# STC15F104_IR_RelayControl.net
KiCad netlist of a schematic drawn in Altium Designer
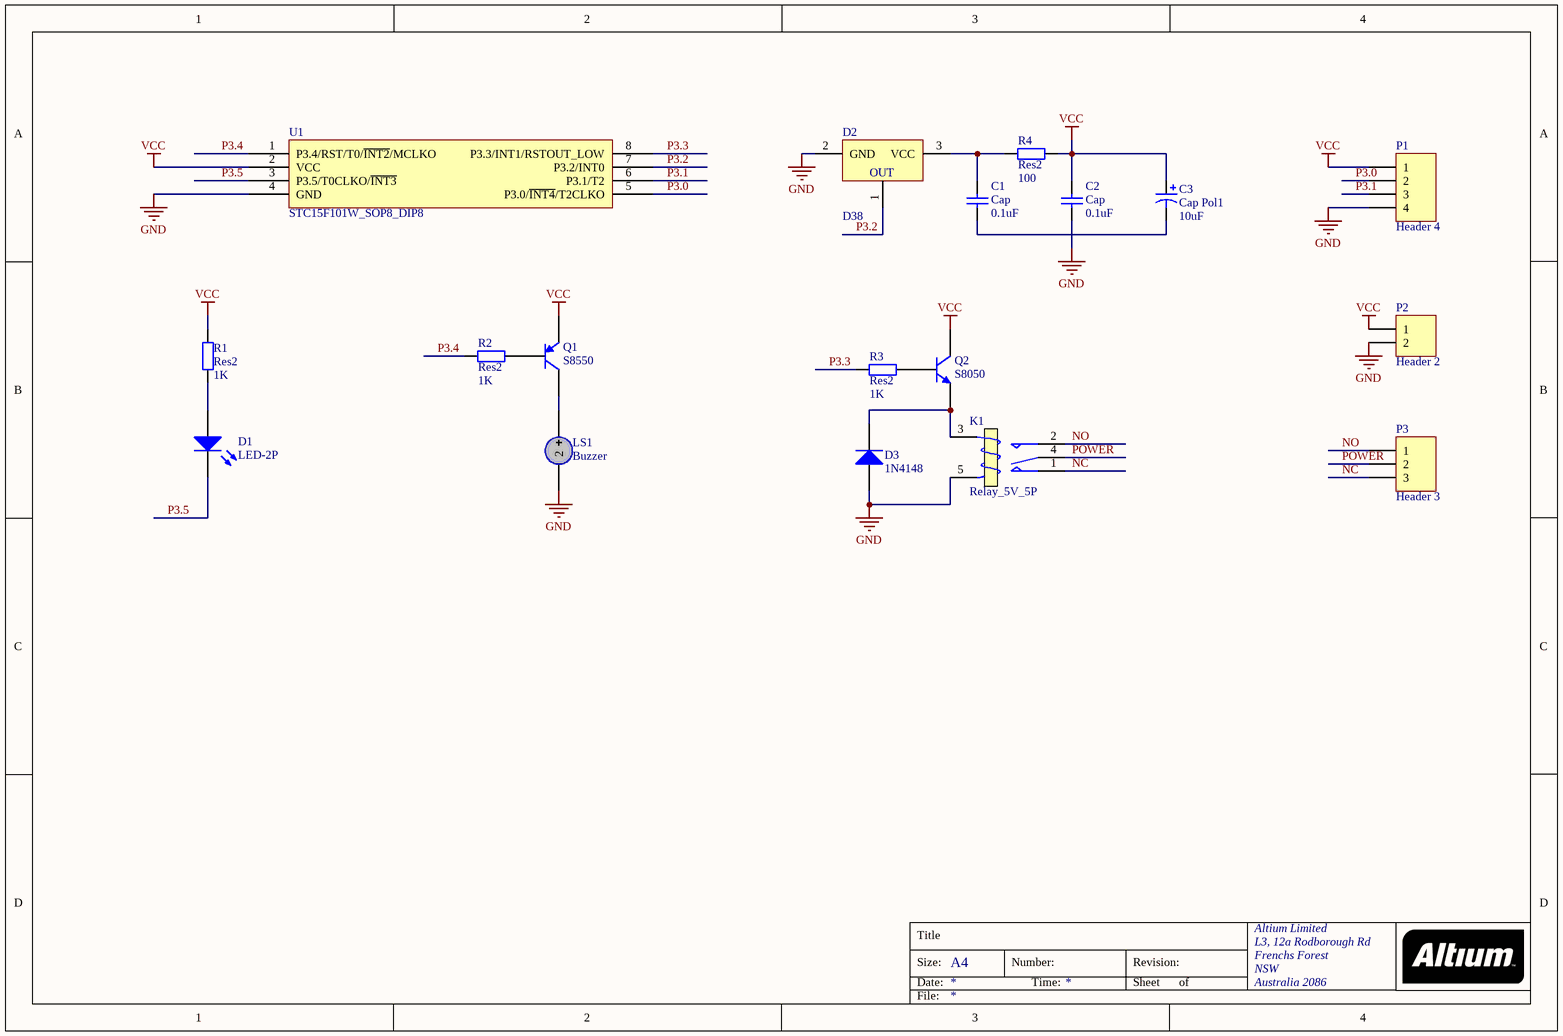
[diagram p0: STC15F104_IR_RelayControl.SchDoc]

(export (version "E")
  (design (tool "Eeschema 10.0.6"))
  (components
    (comp (ref "C1")
      (value "Cap")
      (footprint "0805")
      (description "Capacitor")
      (fields (field (name "ALTIUM_VALUE") "0.1uF") (field (name "PUBLISHER") "Altium Limited"))
      (libsource (lib "Miscellaneous Devices") (part "Cap"))
    )
    (comp (ref "C2")
      (value "Cap")
      (footprint "0805")
      (description "Capacitor")
      (fields (field (name "ALTIUM_VALUE") "0.1uF") (field (name "PUBLISHER") "Altium Limited"))
      (libsource (lib "Miscellaneous Devices") (part "Cap"))
    )
    (comp (ref "C3")
      (value "Cap Pol1")
      (footprint "C1206A")
      (description "Polarized Capacitor (Radial)")
      (fields (field (name "ALTIUM_VALUE") "10uF") (field (name "PUBLISHER") "Altium Limited"))
      (libsource (lib "Miscellaneous Devices") (part "Cap Pol1"))
    )
    (comp (ref "D1")
      (value "LED-2P")
      (footprint "C0805")
      (description "发光二极管")
      (libsource (lib "Devices") (part "LED-2P"))
    )
    (comp (ref "D2")
      (value "D38")
      (footprint "D1838-H3")
      (description "一体化万能接收头")
      (libsource (lib "Devices") (part "D38"))
    )
    (comp (ref "D3")
      (value "1N4148")
      (footprint "C1206A")
      (description "快速开关二极管")
      (libsource (lib "Devices") (part "1N4148"))
    )
    (comp (ref "K1")
      (value "Relay_5V_5P")
      (footprint "RELAY_5V_5P")
      (description "继电器")
      (libsource (lib "Devices") (part "Relay_5V_5P"))
    )
    (comp (ref "LS1")
      (value "Buzzer")
      (footprint "Buzzer")
      (description "蜂鸣")
      (libsource (lib "Devices") (part "Buzzer"))
    )
    (comp (ref "P1")
      (value "Header 4")
      (footprint "HDR1X4")
      (description "Header, 4-Pin")
      (fields (field (name "PUBLISHER") "Altium Limited"))
      (libsource (lib "Miscellaneous Connectors") (part "Header 4"))
    )
    (comp (ref "P2")
      (value "Header 2")
      (footprint "KF301-2P")
      (description "Header, 2-Pin")
      (fields (field (name "PUBLISHER") "Altium Limited"))
      (libsource (lib "Miscellaneous Connectors") (part "Header 2"))
    )
    (comp (ref "P3")
      (value "Header 3")
      (footprint "KF301-3P")
      (description "Header, 3-Pin")
      (fields (field (name "PUBLISHER") "Altium Limited"))
      (libsource (lib "Miscellaneous Connectors") (part "Header 3"))
    )
    (comp (ref "Q1")
      (value "S8550")
      (footprint "TO92")
      (description "PNP 三极管")
      (libsource (lib "Devices") (part "S8550"))
    )
    (comp (ref "Q2")
      (value "S8050")
      (footprint "TO92")
      (description "NPN 三极管")
      (libsource (lib "Devices") (part "S8050"))
    )
    (comp (ref "R1")
      (value "Res2")
      (footprint "0805")
      (description "Resistor")
      (fields (field (name "ALTIUM_VALUE") "1K") (field (name "PUBLISHER") "Altium Limited"))
      (libsource (lib "") (part "Res2_1"))
    )
    (comp (ref "R2")
      (value "Res2")
      (footprint "0805")
      (description "Resistor")
      (fields (field (name "ALTIUM_VALUE") "1K") (field (name "PUBLISHER") "Altium Limited"))
      (libsource (lib "Miscellaneous Devices") (part "Res2"))
    )
    (comp (ref "R3")
      (value "Res2")
      (footprint "0805")
      (description "Resistor")
      (fields (field (name "ALTIUM_VALUE") "1K") (field (name "PUBLISHER") "Altium Limited"))
      (libsource (lib "Miscellaneous Devices") (part "Res2"))
    )
    (comp (ref "R4")
      (value "Res2")
      (footprint "0805")
      (description "Resistor")
      (fields (field (name "ALTIUM_VALUE") "100") (field (name "PUBLISHER") "Altium Limited"))
      (libsource (lib "Miscellaneous Devices") (part "Res2"))
    )
    (comp (ref "U1")
      (value "STC15F101W_SOP8_DIP8")
      (footprint "DIP8_SOP8")
      (libsource (lib "STC") (part "STC15F101W_SOP8_DIP8"))
    )
  )
  (nets
    (net (code "1") (name "/NC") (class "Default")
      (node (ref "K1") (pin "1") (pinfunction "NO_1") (pintype "passive"))
      (node (ref "P3") (pin "3") (pinfunction "3_3") (pintype "passive"))
    )
    (net (code "2") (name "/NO") (class "Default")
      (node (ref "K1") (pin "2") (pinfunction "NC_2") (pintype "passive"))
      (node (ref "P3") (pin "1") (pinfunction "1_1") (pintype "passive"))
    )
    (net (code "3") (name "/P3.0") (class "Default")
      (node (ref "P1") (pin "2") (pinfunction "2_2") (pintype "passive"))
      (node (ref "U1") (pin "5") (pinfunction "P3.0/~{INT4}/T2CLKO_5") (pintype "passive"))
    )
    (net (code "4") (name "/P3.1") (class "Default")
      (node (ref "P1") (pin "3") (pinfunction "3_3") (pintype "passive"))
      (node (ref "U1") (pin "6") (pinfunction "P3.1/T2_6") (pintype "passive"))
    )
    (net (code "5") (name "/P3.2") (class "Default")
      (node (ref "D2") (pin "1") (pinfunction "OUT_1") (pintype "passive"))
      (node (ref "U1") (pin "7") (pinfunction "P3.2/INT0_7") (pintype "passive"))
    )
    (net (code "6") (name "/P3.3") (class "Default")
      (node (ref "R3") (pin "2") (pinfunction "2_2") (pintype "passive"))
      (node (ref "U1") (pin "8") (pinfunction "P3.3/INT1/RSTOUT_LOW_8") (pintype "passive"))
    )
    (net (code "7") (name "/P3.4") (class "Default")
      (node (ref "R2") (pin "2") (pinfunction "2_2") (pintype "passive"))
      (node (ref "U1") (pin "1") (pinfunction "P3.4/RST/T0/~{INT2}/MCLKO_1") (pintype "passive"))
    )
    (net (code "8") (name "/P3.5") (class "Default")
      (node (ref "D1") (pin "2") (pinfunction "K_2") (pintype "passive"))
      (node (ref "U1") (pin "3") (pinfunction "P3.5/T0CLKO/~{INT3}_3") (pintype "passive"))
    )
    (net (code "9") (name "/POWER") (class "Default")
      (node (ref "K1") (pin "4") (pinfunction "COM_4") (pintype "passive"))
      (node (ref "P3") (pin "2") (pinfunction "2_2") (pintype "passive"))
    )
    (net (code "10") (name "GND") (class "Default")
      (node (ref "C2") (pin "2") (pinfunction "2_2") (pintype "passive"))
      (node (ref "D2") (pin "2") (pinfunction "GND_2") (pintype "power_in"))
      (node (ref "D3") (pin "1") (pinfunction "A_1") (pintype "passive"))
      (node (ref "K1") (pin "5") (pinfunction "T2_5") (pintype "passive"))
      (node (ref "LS1") (pin "2") (pinfunction "2_2") (pintype "passive"))
      (node (ref "P1") (pin "4") (pinfunction "4_4") (pintype "passive"))
      (node (ref "P2") (pin "2") (pinfunction "2_2") (pintype "passive"))
      (node (ref "U1") (pin "4") (pinfunction "GND_4") (pintype "passive"))
    )
    (net (code "11") (name "Net-(C1-Pad2)") (class "Default")
      (node (ref "C1") (pin "2") (pinfunction "2_2") (pintype "passive"))
      (node (ref "C3") (pin "2") (pinfunction "2_2") (pintype "passive"))
    )
    (net (code "12") (name "Net-(D1-A)") (class "Default")
      (node (ref "D1") (pin "1") (pinfunction "A_1") (pintype "passive"))
      (node (ref "R1") (pin "2") (pinfunction "2_2") (pintype "passive"))
    )
    (net (code "13") (name "Net-(D2-VCC)") (class "Default")
      (node (ref "C1") (pin "1") (pinfunction "1_1") (pintype "passive"))
      (node (ref "D2") (pin "3") (pinfunction "VCC_3") (pintype "power_in"))
      (node (ref "R4") (pin "2") (pinfunction "2_2") (pintype "passive"))
    )
    (net (code "14") (name "Net-(D3-K)") (class "Default")
      (node (ref "D3") (pin "2") (pinfunction "K_2") (pintype "passive"))
      (node (ref "K1") (pin "3") (pinfunction "T1_3") (pintype "passive"))
      (node (ref "Q2") (pin "1") (pinfunction "E_1") (pintype "passive"))
    )
    (net (code "15") (name "Net-(Q1-B)") (class "Default")
      (node (ref "Q1") (pin "2") (pinfunction "B_2") (pintype "passive"))
      (node (ref "R2") (pin "1") (pinfunction "1_1") (pintype "passive"))
    )
    (net (code "16") (name "Net-(Q1-C)") (class "Default")
      (node (ref "LS1") (pin "1") (pinfunction "1_1") (pintype "passive"))
      (node (ref "Q1") (pin "3") (pinfunction "C_3") (pintype "passive"))
    )
    (net (code "17") (name "Net-(Q2-B)") (class "Default")
      (node (ref "Q2") (pin "2") (pinfunction "B_2") (pintype "passive"))
      (node (ref "R3") (pin "1") (pinfunction "1_1") (pintype "passive"))
    )
    (net (code "18") (name "VCC") (class "Default")
      (node (ref "C2") (pin "1") (pinfunction "1_1") (pintype "passive"))
      (node (ref "C3") (pin "1") (pinfunction "1_1") (pintype "passive"))
      (node (ref "P1") (pin "1") (pinfunction "1_1") (pintype "passive"))
      (node (ref "P2") (pin "1") (pinfunction "1_1") (pintype "passive"))
      (node (ref "Q1") (pin "1") (pinfunction "E_1") (pintype "passive"))
      (node (ref "Q2") (pin "3") (pinfunction "C_3") (pintype "passive"))
      (node (ref "R1") (pin "1") (pinfunction "1_1") (pintype "passive"))
      (node (ref "R4") (pin "1") (pinfunction "1_1") (pintype "passive"))
      (node (ref "U1") (pin "2") (pinfunction "VCC_2") (pintype "passive"))
    )
  )
)
